# Voltage_Feedback_v2.net
KiCad netlist of a schematic drawn in EAGLE
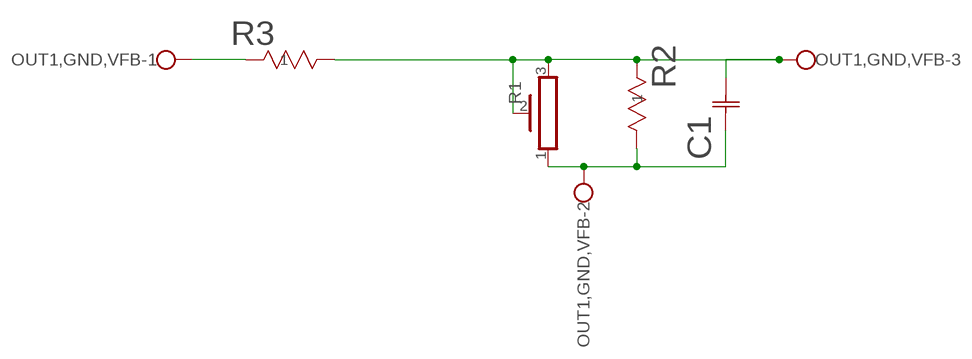
[diagram p0: schematic, sheet 1]

(export (version "E")
  (design (tool "Eeschema 10.0.6"))
  (components
    (comp (ref "C1")
      (value "564R60GAD10CAP_60GAD10_VIS")
      (footprint "eagle-import:CAP_60GAD10_VIS")
      (fields
        (field (name "MANUFACTURER_PART_NUMBER") "564R60GAD10")
        (field (name "COPYRIGHT") "Copyright (C) 2024 Ultra Librarian. All rights reserved.")
      )
      (libsource (lib "eagle-import") (part "564R60GAD10CAP_60GAD10_VIS"))
    )
    (comp (ref "OUT1,GND,VFB")
      (value "W237-03P")
      (footprint "eagle-import:W237-133")
      (libsource (lib "eagle-import") (part "W237-03P"))
    )
    (comp (ref "R1")
      (value "PV36P")
      (footprint "eagle-import:PV36P")
      (fields (field (name "MANUFACTURER") "BOURNS"))
      (libsource (lib "eagle-import") (part "PV36P"))
    )
    (comp (ref "R2")
      (value "CF14JT10K0STA_CF14_STP")
      (footprint "eagle-import:STA_CF14_STP")
      (fields
        (field (name "MANUFACTURER_PART_NUMBER") "CF14JT10K0")
        (field (name "COPYRIGHT") "Copyright (C) 2024 Ultra Librarian. All rights reserved.")
      )
      (libsource (lib "eagle-import") (part "CF14JT10K0STA_CF14_STP"))
    )
    (comp (ref "R3")
      (value "CF14JT10K0STA_CF14_STP")
      (footprint "eagle-import:STA_CF14_STP")
      (fields
        (field (name "MANUFACTURER_PART_NUMBER") "CF14JT10K0")
        (field (name "COPYRIGHT") "Copyright (C) 2024 Ultra Librarian. All rights reserved.")
      )
      (libsource (lib "eagle-import") (part "CF14JT10K0STA_CF14_STP"))
    )
  )
  (nets
    (net (code "1") (name "Net-(OUT1,GND,VFBA-KL)") (class "Default")
      (node (ref "OUT1,GND,VFB") (pin "1") (pinfunction "KL_1") (pintype "passive"))
      (node (ref "R3") (pin "1") (pinfunction "1_1") (pintype "passive"))
    )
    (net (code "2") (name "Net-(OUT1,GND,VFBB-KL)") (class "Default")
      (node (ref "C1") (pin "1") (pinfunction "1_1") (pintype "passive"))
      (node (ref "OUT1,GND,VFB") (pin "2") (pinfunction "KL_2") (pintype "passive"))
      (node (ref "R1") (pin "1") (pinfunction "P$1_1") (pintype "passive"))
      (node (ref "R2") (pin "2") (pinfunction "2_2") (pintype "passive"))
    )
    (net (code "3") (name "Net-(OUT1,GND,VFBC-KL)") (class "Default")
      (node (ref "C1") (pin "2") (pinfunction "2_2") (pintype "passive"))
      (node (ref "OUT1,GND,VFB") (pin "3") (pinfunction "KL_3") (pintype "passive"))
      (node (ref "R1") (pin "2") (pinfunction "P$2_2") (pintype "passive"))
      (node (ref "R1") (pin "3") (pinfunction "P$3_3") (pintype "passive"))
      (node (ref "R2") (pin "1") (pinfunction "1_1") (pintype "passive"))
      (node (ref "R3") (pin "2") (pinfunction "2_2") (pintype "passive"))
    )
  )
)
